# Power.net
KiCad netlist of a schematic drawn in Altium Designer
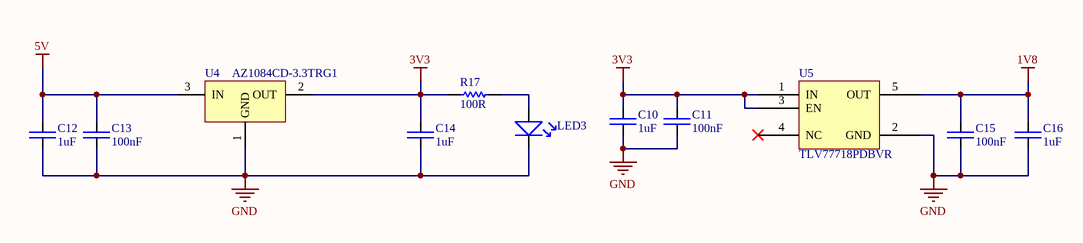
[diagram p0: Power.SchDoc]

(export (version "E")
  (design (tool "Eeschema 10.0.6"))
  (components
    (comp (ref "C10")
      (value "1uF")
      (footprint "CAP-0805")
      (description "Capacitor chip unpolarized. 0805")
      (libsource (lib "Master") (part "CAP-0805"))
    )
    (comp (ref "C11")
      (value "100nF")
      (footprint "CAP-0603")
      (description "Capacitor chip unpolarized. 0603")
      (libsource (lib "Master") (part "CAP-0603"))
    )
    (comp (ref "C12")
      (value "1uF")
      (footprint "CAP-0805")
      (description "Capacitor chip unpolarized. 0805")
      (libsource (lib "Master") (part "CAP-0805"))
    )
    (comp (ref "C13")
      (value "100nF")
      (footprint "CAP-0603")
      (description "Capacitor chip unpolarized. 0603")
      (libsource (lib "Master") (part "CAP-0603"))
    )
    (comp (ref "C14")
      (value "1uF")
      (footprint "CAP-0805")
      (description "Capacitor chip unpolarized. 0805")
      (libsource (lib "Master") (part "CAP-0805"))
    )
    (comp (ref "C15")
      (value "100nF")
      (footprint "CAP-0603")
      (description "Capacitor chip unpolarized. 0603")
      (libsource (lib "Master") (part "CAP-0603"))
    )
    (comp (ref "C16")
      (value "1uF")
      (footprint "CAP-0805")
      (description "Capacitor chip unpolarized. 0805")
      (libsource (lib "Master") (part "CAP-0805"))
    )
    (comp (ref "LED3") (value "0603 LED") (footprint "0603 LED") (libsource (lib "Master") (part "0603 LED")))
    (comp (ref "R17")
      (value "100R")
      (footprint "RES-0603")
      (description "Resistor chip. 0603")
      (libsource (lib "Master") (part "RES-0603"))
    )
    (comp (ref "U4")
      (value "AZ1084CD-3.3TRG1")
      (footprint "AZ1084CD-3.3TRG1")
      (description "3V3 LDO 1A 1.5V Dropout")
      (libsource (lib "Master") (part "AZ1084CD-3.3TRG1"))
    )
    (comp (ref "U5")
      (value "TLV77718PDBVR")
      (footprint "TLV77718PDBVR")
      (description "LDO 1.8V 1A")
      (libsource (lib "Master") (part "TLV77718PDBVR"))
    )
  )
  (nets
    (net (code "1") (name "1V8") (class "Default")
      (node (ref "C15") (pin "2") (pintype "passive"))
      (node (ref "C16") (pin "2") (pintype "passive"))
      (node (ref "U5") (pin "5") (pinfunction "OUT_5") (pintype "passive"))
    )
    (net (code "2") (name "3V3") (class "Default")
      (node (ref "C10") (pin "2") (pintype "passive"))
      (node (ref "C11") (pin "2") (pintype "passive"))
      (node (ref "C14") (pin "2") (pintype "passive"))
      (node (ref "R17") (pin "1") (pintype "passive"))
      (node (ref "U4") (pin "2") (pinfunction "OUT_2") (pintype "passive"))
      (node (ref "U5") (pin "1") (pinfunction "IN_1") (pintype "passive"))
      (node (ref "U5") (pin "3") (pinfunction "EN_3") (pintype "passive"))
    )
    (net (code "3") (name "5V") (class "Default")
      (node (ref "C12") (pin "2") (pintype "passive"))
      (node (ref "C13") (pin "2") (pintype "passive"))
      (node (ref "U4") (pin "3") (pinfunction "IN_3") (pintype "passive"))
    )
    (net (code "4") (name "GND") (class "Default")
      (node (ref "C10") (pin "1") (pintype "passive"))
      (node (ref "C11") (pin "1") (pintype "passive"))
      (node (ref "C12") (pin "1") (pintype "passive"))
      (node (ref "C13") (pin "1") (pintype "passive"))
      (node (ref "C14") (pin "1") (pintype "passive"))
      (node (ref "C15") (pin "1") (pintype "passive"))
      (node (ref "C16") (pin "1") (pintype "passive"))
      (node (ref "LED3") (pin "2") (pinfunction "5_2") (pintype "passive"))
      (node (ref "U4") (pin "1") (pinfunction "GND_1") (pintype "passive"))
      (node (ref "U5") (pin "2") (pinfunction "GND_2") (pintype "passive"))
    )
    (net (code "5") (name "Net-(LED3-6)") (class "Default")
      (node (ref "LED3") (pin "1") (pinfunction "6_1") (pintype "passive"))
      (node (ref "R17") (pin "2") (pintype "passive"))
    )
    (net (code "6") (name "unconnected-(U5-NC-Pad4)") (class "Default")
      (node (ref "U5") (pin "4") (pinfunction "NC_4") (pintype "passive+no_connect"))
    )
  )
)
